# neojoint3-090.net
KiCad netlist of a schematic drawn in EAGLE
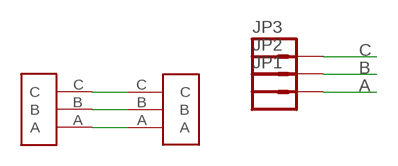
[diagram p0: schematic, sheet 1]

(export (version "E")
  (design (tool "Eeschema 10.0.6"))
  (components
    (comp (ref "JP1")
      (value "M01PTH")
      (footprint "eagle-import:1X01")
      (libsource (lib "eagle-import") (part "M01PTH"))
    )
    (comp (ref "JP2")
      (value "M01PTH")
      (footprint "eagle-import:1X01")
      (libsource (lib "eagle-import") (part "M01PTH"))
    )
    (comp (ref "JP3")
      (value "M01PTH")
      (footprint "eagle-import:1X01")
      (libsource (lib "eagle-import") (part "M01PTH"))
    )
    (comp (ref "U$1")
      (value "LED_STRIP_3P")
      (footprint "eagle-import:LEDSTRIP-3P")
      (libsource (lib "eagle-import") (part "LED_STRIP_3P"))
    )
    (comp (ref "U$2")
      (value "LED_STRIP_3P")
      (footprint "eagle-import:LEDSTRIP-3P")
      (libsource (lib "eagle-import") (part "LED_STRIP_3P"))
    )
  )
  (nets
    (net (code "1") (name "/A") (class "Default")
      (node (ref "JP1") (pin "1") (pinfunction "1_1") (pintype "passive"))
      (node (ref "U$1") (pin "A") (pinfunction "A_A") (pintype "bidirectional"))
      (node (ref "U$2") (pin "A") (pinfunction "A_A") (pintype "bidirectional"))
    )
    (net (code "2") (name "/B") (class "Default")
      (node (ref "JP2") (pin "1") (pinfunction "1_1") (pintype "passive"))
      (node (ref "U$1") (pin "B") (pinfunction "B_B") (pintype "bidirectional"))
      (node (ref "U$2") (pin "B") (pinfunction "B_B") (pintype "bidirectional"))
    )
    (net (code "3") (name "/C") (class "Default")
      (node (ref "JP3") (pin "1") (pinfunction "1_1") (pintype "passive"))
      (node (ref "U$1") (pin "C") (pinfunction "C_C") (pintype "bidirectional"))
      (node (ref "U$2") (pin "C") (pinfunction "C_C") (pintype "bidirectional"))
    )
  )
)
